# HID2JOY.net
KiCad netlist of a schematic drawn in EAGLE
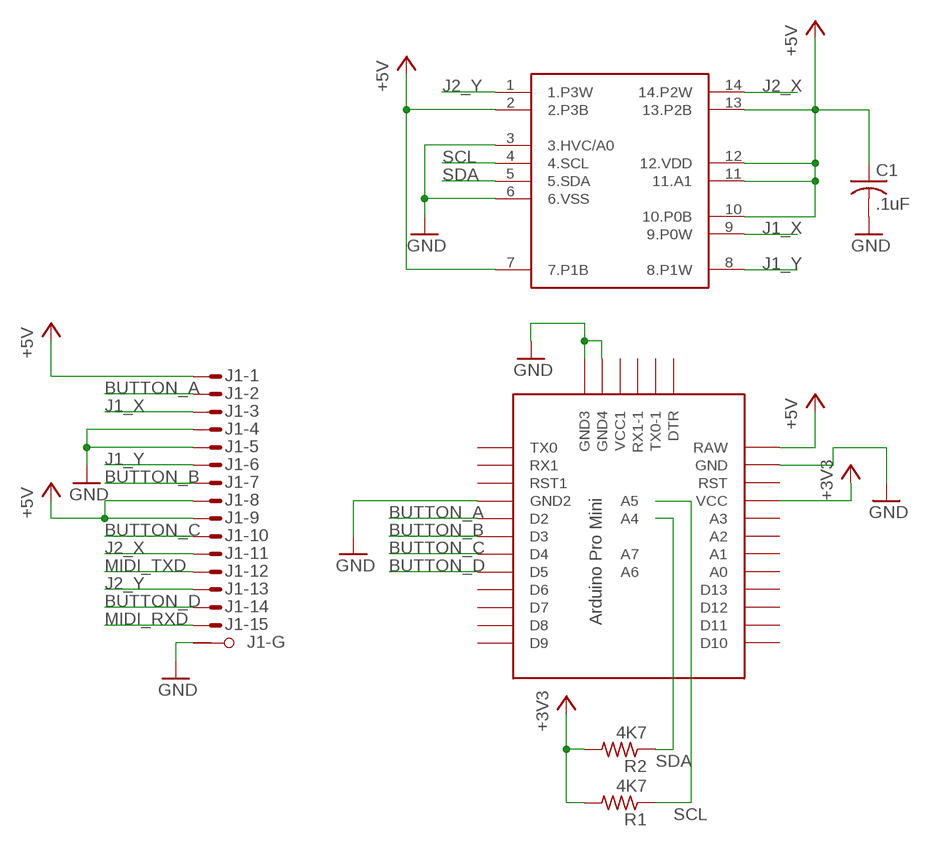
[diagram p0: schematic, sheet 1]

(export (version "E")
  (design (tool "Eeschema 10.0.6"))
  (components
    (comp (ref "C1")
      (value ".1uF")
      (footprint "eagle-import:C0603")
      (libsource (lib "eagle-import") (part "C-USC0603"))
    )
    (comp (ref "J1")
      (value "M15HPS")
      (footprint "eagle-import:M15HP")
      (libsource (lib "eagle-import") (part "M15HPS"))
    )
    (comp (ref "R1")
      (value "4K7")
      (footprint "eagle-import:R0603")
      (libsource (lib "eagle-import") (part "R-US_R0603"))
    )
    (comp (ref "R2")
      (value "4K7")
      (footprint "eagle-import:R0603")
      (libsource (lib "eagle-import") (part "R-US_R0603"))
    )
    (comp (ref "U$1")
      (value "PRO-MINI-2")
      (footprint "eagle-import:PRO-MINI-2")
      (libsource (lib "eagle-import") (part "PRO-MINI-2"))
    )
    (comp (ref "U1")
      (value "PCM44X2TSSOP")
      (footprint "eagle-import:TSSOP14")
      (libsource (lib "eagle-import") (part "PCM44X2TSSOP"))
    )
  )
  (nets
    (net (code "1") (name "+3V3") (class "Default")
      (node (ref "R1") (pin "2") (pinfunction "2_2") (pintype "passive"))
      (node (ref "R2") (pin "2") (pinfunction "2_2") (pintype "passive"))
      (node (ref "U$1") (pin "VCC") (pinfunction "VCC_VCC") (pintype "bidirectional"))
    )
    (net (code "2") (name "+5V") (class "Default")
      (node (ref "C1") (pin "1") (pinfunction "1_1") (pintype "passive"))
      (node (ref "J1") (pin "1") (pinfunction "M_1") (pintype "passive"))
      (node (ref "J1") (pin "8") (pinfunction "M_8") (pintype "passive"))
      (node (ref "J1") (pin "9") (pinfunction "M_9") (pintype "passive"))
      (node (ref "U$1") (pin "RAW") (pinfunction "RAW_RAW") (pintype "bidirectional"))
      (node (ref "U1") (pin "10") (pinfunction "10.P0B_10") (pintype "bidirectional"))
      (node (ref "U1") (pin "11") (pinfunction "11.A1_11") (pintype "input"))
      (node (ref "U1") (pin "12") (pinfunction "12.VDD_12") (pintype "power_in"))
      (node (ref "U1") (pin "13") (pinfunction "13.P2B_13") (pintype "bidirectional"))
      (node (ref "U1") (pin "2") (pinfunction "2.P3B_2") (pintype "bidirectional"))
      (node (ref "U1") (pin "7") (pinfunction "7.P1B_7") (pintype "bidirectional"))
    )
    (net (code "3") (name "/BUTTON_A") (class "Default")
      (node (ref "J1") (pin "2") (pinfunction "M_2") (pintype "passive"))
      (node (ref "U$1") (pin "D2") (pinfunction "D2_D2") (pintype "bidirectional"))
    )
    (net (code "4") (name "/BUTTON_B") (class "Default")
      (node (ref "J1") (pin "7") (pinfunction "M_7") (pintype "passive"))
      (node (ref "U$1") (pin "D3") (pinfunction "D3_D3") (pintype "bidirectional"))
    )
    (net (code "5") (name "/BUTTON_C") (class "Default")
      (node (ref "J1") (pin "10") (pinfunction "M_10") (pintype "passive"))
      (node (ref "U$1") (pin "D4") (pinfunction "D4_D4") (pintype "bidirectional"))
    )
    (net (code "6") (name "/BUTTON_D") (class "Default")
      (node (ref "J1") (pin "14") (pinfunction "M_14") (pintype "passive"))
      (node (ref "U$1") (pin "D5") (pinfunction "D5_D5") (pintype "bidirectional"))
    )
    (net (code "7") (name "/J1_X") (class "Default")
      (node (ref "J1") (pin "3") (pinfunction "M_3") (pintype "passive"))
      (node (ref "U1") (pin "9") (pinfunction "9.P0W_9") (pintype "bidirectional"))
    )
    (net (code "8") (name "/J1_Y") (class "Default")
      (node (ref "J1") (pin "6") (pinfunction "M_6") (pintype "passive"))
      (node (ref "U1") (pin "8") (pinfunction "8.P1W_8") (pintype "bidirectional"))
    )
    (net (code "9") (name "/J2_X") (class "Default")
      (node (ref "J1") (pin "11") (pinfunction "M_11") (pintype "passive"))
      (node (ref "U1") (pin "14") (pinfunction "14.P2W_14") (pintype "bidirectional"))
    )
    (net (code "10") (name "/J2_Y") (class "Default")
      (node (ref "J1") (pin "13") (pinfunction "M_13") (pintype "passive"))
      (node (ref "U1") (pin "1") (pinfunction "1.P3W_1") (pintype "bidirectional"))
    )
    (net (code "11") (name "/MIDI_RXD") (class "Default")
      (node (ref "J1") (pin "15") (pinfunction "M_15") (pintype "passive"))
    )
    (net (code "12") (name "/MIDI_TXD") (class "Default")
      (node (ref "J1") (pin "12") (pinfunction "M_12") (pintype "passive"))
    )
    (net (code "13") (name "/SCL") (class "Default")
      (node (ref "R1") (pin "1") (pinfunction "1_1") (pintype "passive"))
      (node (ref "U$1") (pin "A5") (pinfunction "A5_A5") (pintype "bidirectional"))
      (node (ref "U1") (pin "4") (pinfunction "4.SCL_4") (pintype "bidirectional"))
    )
    (net (code "14") (name "/SDA") (class "Default")
      (node (ref "R2") (pin "1") (pinfunction "1_1") (pintype "passive"))
      (node (ref "U$1") (pin "A4") (pinfunction "A4_A4") (pintype "bidirectional"))
      (node (ref "U1") (pin "5") (pinfunction "5.SDA_5") (pintype "bidirectional"))
    )
    (net (code "15") (name "GND") (class "Default")
      (node (ref "C1") (pin "2") (pinfunction "2_2") (pintype "passive"))
      (node (ref "J1") (pin "4") (pinfunction "M_4") (pintype "passive"))
      (node (ref "J1") (pin "5") (pinfunction "M_5") (pintype "passive"))
      (node (ref "J1") (pin "G1") (pinfunction "G1_G1") (pintype "passive"))
      (node (ref "U$1") (pin "GND") (pinfunction "GND_GND") (pintype "bidirectional"))
      (node (ref "U$1") (pin "GND1") (pinfunction "GND2_GND1") (pintype "bidirectional"))
      (node (ref "U$1") (pin "GND2") (pinfunction "GND3_GND2") (pintype "bidirectional"))
      (node (ref "U$1") (pin "GND3") (pinfunction "GND4_GND3") (pintype "bidirectional"))
      (node (ref "U1") (pin "3") (pinfunction "3.HVC/A0_3") (pintype "input"))
      (node (ref "U1") (pin "6") (pinfunction "6.VSS_6") (pintype "power_in"))
    )
    (net (code "16") (name "unconnected-(J1-PadG2)") (class "Default")
      (node (ref "J1") (pin "G2") (pinfunction "G2_G2") (pintype "passive"))
    )
    (net (code "17") (name "unconnected-(U$1-PadA0)") (class "Default")
      (node (ref "U$1") (pin "A0") (pinfunction "A0_A0") (pintype "bidirectional"))
    )
    (net (code "18") (name "unconnected-(U$1-PadA1)") (class "Default")
      (node (ref "U$1") (pin "A1") (pinfunction "A1_A1") (pintype "bidirectional"))
    )
    (net (code "19") (name "unconnected-(U$1-PadA2)") (class "Default")
      (node (ref "U$1") (pin "A2") (pinfunction "A2_A2") (pintype "bidirectional"))
    )
    (net (code "20") (name "unconnected-(U$1-PadA3)") (class "Default")
      (node (ref "U$1") (pin "A3") (pinfunction "A3_A3") (pintype "bidirectional"))
    )
    (net (code "21") (name "unconnected-(U$1-PadA6)") (class "Default")
      (node (ref "U$1") (pin "A6") (pinfunction "A6_A6") (pintype "bidirectional"))
    )
    (net (code "22") (name "unconnected-(U$1-PadA7)") (class "Default")
      (node (ref "U$1") (pin "A7") (pinfunction "A7_A7") (pintype "bidirectional"))
    )
    (net (code "23") (name "unconnected-(U$1-PadD6)") (class "Default")
      (node (ref "U$1") (pin "D6") (pinfunction "D6_D6") (pintype "bidirectional"))
    )
    (net (code "24") (name "unconnected-(U$1-PadD7)") (class "Default")
      (node (ref "U$1") (pin "D7") (pinfunction "D7_D7") (pintype "bidirectional"))
    )
    (net (code "25") (name "unconnected-(U$1-PadD8)") (class "Default")
      (node (ref "U$1") (pin "D8") (pinfunction "D8_D8") (pintype "bidirectional"))
    )
    (net (code "26") (name "unconnected-(U$1-PadD9)") (class "Default")
      (node (ref "U$1") (pin "D9") (pinfunction "D9_D9") (pintype "bidirectional"))
    )
    (net (code "27") (name "unconnected-(U$1-PadD10)") (class "Default")
      (node (ref "U$1") (pin "D10") (pinfunction "D10_D10") (pintype "bidirectional"))
    )
    (net (code "28") (name "unconnected-(U$1-PadD11)") (class "Default")
      (node (ref "U$1") (pin "D11") (pinfunction "D11_D11") (pintype "bidirectional"))
    )
    (net (code "29") (name "unconnected-(U$1-PadD12)") (class "Default")
      (node (ref "U$1") (pin "D12") (pinfunction "D12_D12") (pintype "bidirectional"))
    )
    (net (code "30") (name "unconnected-(U$1-PadD13)") (class "Default")
      (node (ref "U$1") (pin "D13") (pinfunction "D13_D13") (pintype "bidirectional"))
    )
    (net (code "31") (name "unconnected-(U$1-PadDTR)") (class "Default")
      (node (ref "U$1") (pin "DTR") (pinfunction "DTR_DTR") (pintype "bidirectional"))
    )
    (net (code "32") (name "unconnected-(U$1-PadRST)") (class "Default")
      (node (ref "U$1") (pin "RST") (pinfunction "RST_RST") (pintype "bidirectional"))
    )
    (net (code "33") (name "unconnected-(U$1-PadRST1)") (class "Default")
      (node (ref "U$1") (pin "RST1") (pinfunction "RST1_RST1") (pintype "bidirectional"))
    )
    (net (code "34") (name "unconnected-(U$1-PadRX1)") (class "Default")
      (node (ref "U$1") (pin "RX1") (pinfunction "RX1_RX1") (pintype "bidirectional"))
    )
    (net (code "35") (name "unconnected-(U$1-PadRX1-1)") (class "Default")
      (node (ref "U$1") (pin "RX1-1") (pinfunction "RX1-1_RX1-1") (pintype "bidirectional"))
    )
    (net (code "36") (name "unconnected-(U$1-PadTX0)") (class "Default")
      (node (ref "U$1") (pin "TX0") (pinfunction "TX0_TX0") (pintype "bidirectional"))
    )
    (net (code "37") (name "unconnected-(U$1-PadTX0-1)") (class "Default")
      (node (ref "U$1") (pin "TX0-1") (pinfunction "TX0-1_TX0-1") (pintype "bidirectional"))
    )
    (net (code "38") (name "unconnected-(U$1-PadVCC1)") (class "Default")
      (node (ref "U$1") (pin "VCC1") (pinfunction "VCC1_VCC1") (pintype "bidirectional"))
    )
  )
)
